# Motherboard.net
KiCad netlist of a schematic drawn in EAGLE
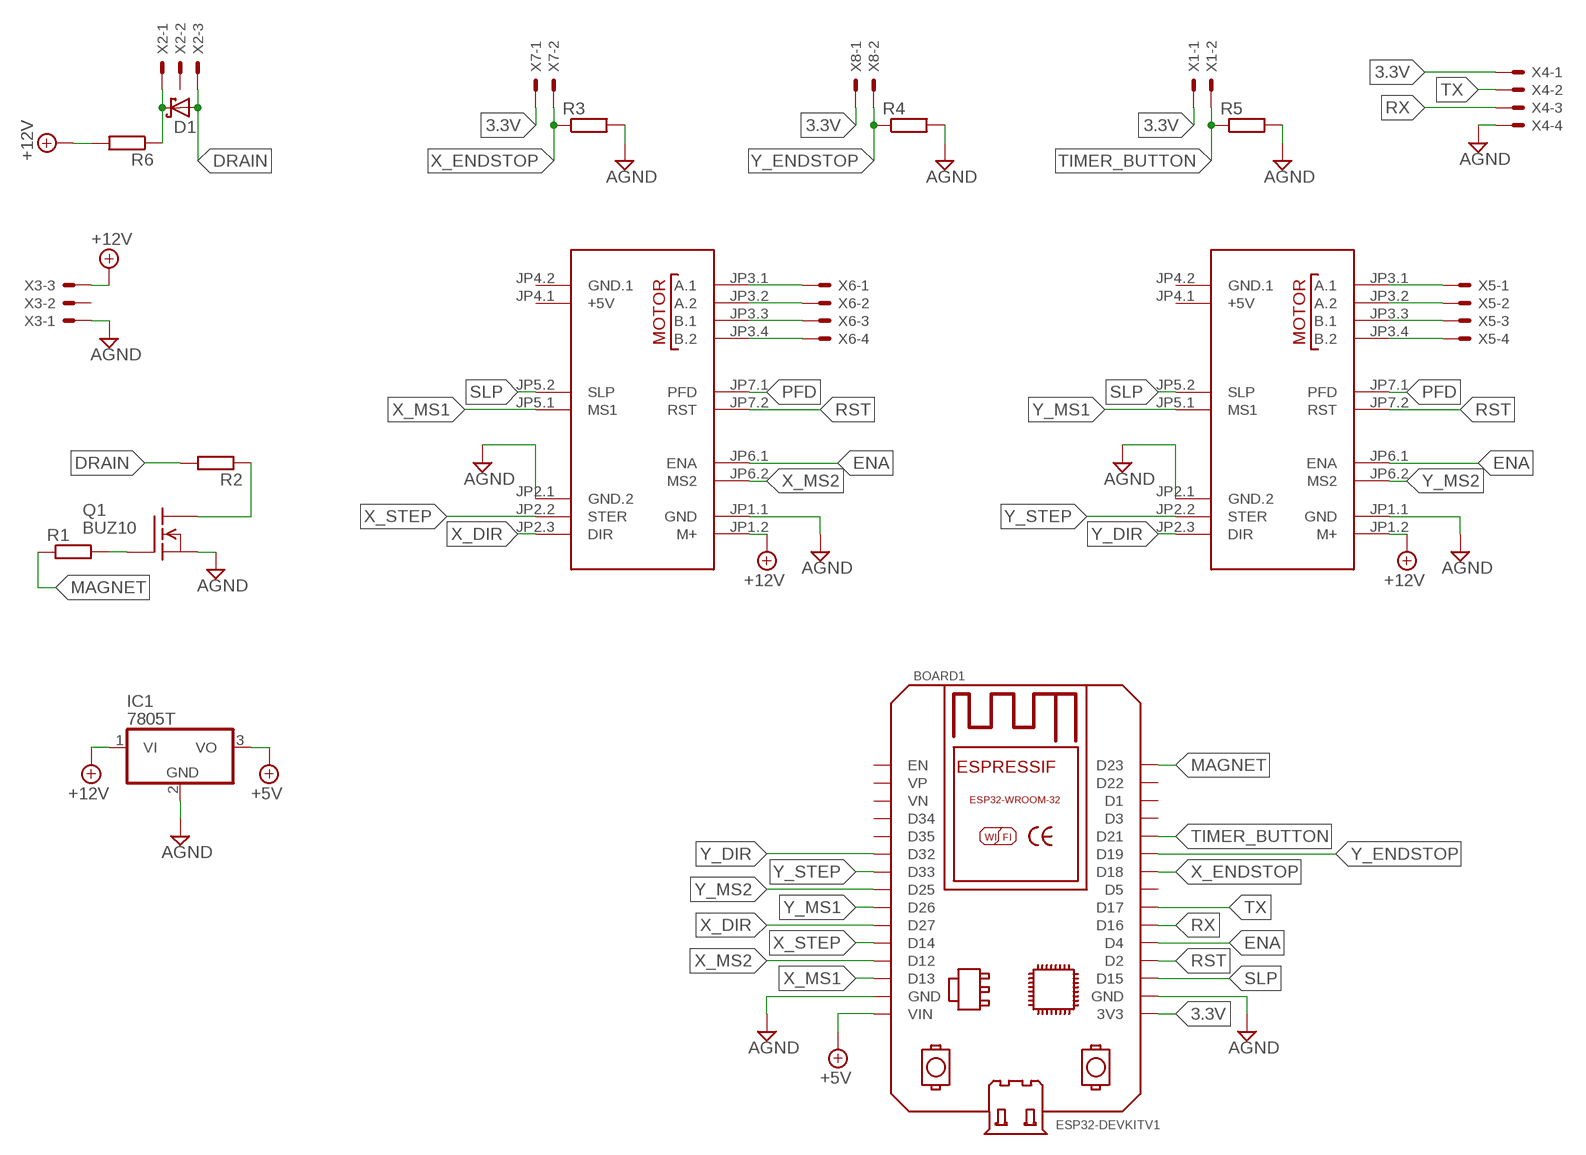
[diagram p0: schematic, sheet 1]

(export (version "E")
  (design (tool "Eeschema 10.0.6"))
  (components
    (comp (ref "BOARD1")
      (value "ESP32DEVKITV1")
      (footprint "eagle-import:ESP32-DEVKITV1")
      (libsource (lib "eagle-import") (part "ESP32DEVKITV1"))
    )
    (comp (ref "D1")
      (value "SCHOTTKY-DIODECB417-15")
      (footprint "eagle-import:CB417-15")
      (libsource (lib "eagle-import") (part "SCHOTTKY-DIODECB417-15"))
    )
    (comp (ref "IC1")
      (value "7805T")
      (footprint "eagle-import:TO220H")
      (libsource (lib "eagle-import") (part "78T05"))
    )
    (comp (ref "Q1")
      (value "BUZ10")
      (footprint "eagle-import:TO220")
      (libsource (lib "eagle-import") (part "BUZ10"))
    )
    (comp (ref "R1")
      (value "R-EU_R0603")
      (footprint "eagle-import:R0603")
      (libsource (lib "eagle-import") (part "R-EU_R0603"))
    )
    (comp (ref "R2")
      (value "R-EU_R0603")
      (footprint "eagle-import:R0603")
      (libsource (lib "eagle-import") (part "R-EU_R0603"))
    )
    (comp (ref "R3")
      (value "R-EU_R0603")
      (footprint "eagle-import:R0603")
      (libsource (lib "eagle-import") (part "R-EU_R0603"))
    )
    (comp (ref "R4")
      (value "R-EU_R0603")
      (footprint "eagle-import:R0603")
      (libsource (lib "eagle-import") (part "R-EU_R0603"))
    )
    (comp (ref "R5")
      (value "R-EU_R0603")
      (footprint "eagle-import:R0603")
      (libsource (lib "eagle-import") (part "R-EU_R0603"))
    )
    (comp (ref "R6")
      (value "R-EU_R0603")
      (footprint "eagle-import:R0603")
      (libsource (lib "eagle-import") (part "R-EU_R0603"))
    )
    (comp (ref "U$1")
      (value "STEPPER-MOTOR-EASY-DRIVER")
      (footprint "eagle-import:STEPPER-MOTOR-EASY-DRIVER")
      (libsource (lib "eagle-import") (part "STEPPER-MOTOR-EASY-DRIVER"))
    )
    (comp (ref "U$2")
      (value "STEPPER-MOTOR-EASY-DRIVER")
      (footprint "eagle-import:STEPPER-MOTOR-EASY-DRIVER")
      (libsource (lib "eagle-import") (part "STEPPER-MOTOR-EASY-DRIVER"))
    )
    (comp (ref "X1")
      (value "22-23-2021")
      (footprint "eagle-import:22-23-2021")
      (fields (field (name "MF") "MOLEX"))
      (libsource (lib "eagle-import") (part "22-23-2021"))
    )
    (comp (ref "X2")
      (value "22-23-2031")
      (footprint "eagle-import:22-23-2031")
      (fields (field (name "MF") "MOLEX"))
      (libsource (lib "eagle-import") (part "22-23-2031"))
    )
    (comp (ref "X3")
      (value "22-23-2031")
      (footprint "eagle-import:22-23-2031")
      (fields (field (name "MF") "MOLEX"))
      (libsource (lib "eagle-import") (part "22-23-2031"))
    )
    (comp (ref "X4")
      (value "22-23-2041")
      (footprint "eagle-import:22-23-2041")
      (fields (field (name "MF") "MOLEX"))
      (libsource (lib "eagle-import") (part "22-23-2041"))
    )
    (comp (ref "X5")
      (value "22-23-2041")
      (footprint "eagle-import:22-23-2041")
      (fields (field (name "MF") "MOLEX"))
      (libsource (lib "eagle-import") (part "22-23-2041"))
    )
    (comp (ref "X6")
      (value "22-23-2041")
      (footprint "eagle-import:22-23-2041")
      (fields (field (name "MF") "MOLEX"))
      (libsource (lib "eagle-import") (part "22-23-2041"))
    )
    (comp (ref "X7")
      (value "22-23-2021")
      (footprint "eagle-import:22-23-2021")
      (fields (field (name "MF") "MOLEX"))
      (libsource (lib "eagle-import") (part "22-23-2021"))
    )
    (comp (ref "X8")
      (value "22-23-2021")
      (footprint "eagle-import:22-23-2021")
      (fields (field (name "MF") "MOLEX"))
      (libsource (lib "eagle-import") (part "22-23-2021"))
    )
  )
  (nets
    (net (code "1") (name "+5V") (class "Default")
      (node (ref "BOARD1") (pin "VIN") (pinfunction "VIN_VIN") (pintype "bidirectional"))
      (node (ref "IC1") (pin "3") (pinfunction "VO_3") (pintype "passive"))
    )
    (net (code "2") (name "+12V") (class "Default")
      (node (ref "IC1") (pin "1") (pinfunction "VI_1") (pintype "input"))
      (node (ref "R6") (pin "2") (pinfunction "2_2") (pintype "passive"))
      (node (ref "U$1") (pin "JP1.2") (pinfunction "M+_JP1.2") (pintype "bidirectional"))
      (node (ref "U$2") (pin "JP1.2") (pinfunction "M+_JP1.2") (pintype "bidirectional"))
      (node (ref "X3") (pin "3") (pinfunction "S_3") (pintype "passive"))
    )
    (net (code "3") (name "3.3V") (class "Default")
      (node (ref "BOARD1") (pin "3V3") (pinfunction "3V3_3V3") (pintype "bidirectional"))
      (node (ref "X1") (pin "1") (pinfunction "S_1") (pintype "passive"))
      (node (ref "X4") (pin "1") (pinfunction "S_1") (pintype "passive"))
      (node (ref "X7") (pin "1") (pinfunction "S_1") (pintype "passive"))
      (node (ref "X8") (pin "1") (pinfunction "S_1") (pintype "passive"))
    )
    (net (code "4") (name "AGND") (class "Default")
      (node (ref "BOARD1") (pin "GND") (pinfunction "GND_GND") (pintype "bidirectional"))
      (node (ref "BOARD1") (pin "GND@1") (pinfunction "GND_GND@1") (pintype "bidirectional"))
      (node (ref "IC1") (pin "2") (pinfunction "GND_2") (pintype "passive"))
      (node (ref "Q1") (pin "3") (pinfunction "S_3") (pintype "passive"))
      (node (ref "R3") (pin "2") (pinfunction "2_2") (pintype "passive"))
      (node (ref "R4") (pin "2") (pinfunction "2_2") (pintype "passive"))
      (node (ref "R5") (pin "2") (pinfunction "2_2") (pintype "passive"))
      (node (ref "U$1") (pin "JP1.1") (pinfunction "GND_JP1.1") (pintype "bidirectional"))
      (node (ref "U$1") (pin "JP2.1") (pinfunction "GND.2_JP2.1") (pintype "bidirectional"))
      (node (ref "U$2") (pin "JP1.1") (pinfunction "GND_JP1.1") (pintype "bidirectional"))
      (node (ref "U$2") (pin "JP2.1") (pinfunction "GND.2_JP2.1") (pintype "bidirectional"))
      (node (ref "X3") (pin "1") (pinfunction "S_1") (pintype "passive"))
      (node (ref "X4") (pin "4") (pinfunction "S_4") (pintype "passive"))
    )
    (net (code "5") (name "DRAIN") (class "Default")
      (node (ref "D1") (pin "A") (pinfunction "A_A") (pintype "passive"))
      (node (ref "R2") (pin "2") (pinfunction "2_2") (pintype "passive"))
      (node (ref "X2") (pin "3") (pinfunction "S_3") (pintype "passive"))
    )
    (net (code "6") (name "ENA") (class "Default")
      (node (ref "BOARD1") (pin "D4") (pinfunction "D4_D4") (pintype "bidirectional"))
      (node (ref "U$1") (pin "JP6.1") (pinfunction "ENA_JP6.1") (pintype "bidirectional"))
      (node (ref "U$2") (pin "JP6.1") (pinfunction "ENA_JP6.1") (pintype "bidirectional"))
    )
    (net (code "7") (name "MAGNET") (class "Default")
      (node (ref "BOARD1") (pin "D23") (pinfunction "D23_D23") (pintype "bidirectional"))
      (node (ref "R1") (pin "1") (pinfunction "1_1") (pintype "passive"))
    )
    (net (code "8") (name "Net-(Q1-D)") (class "Default")
      (node (ref "Q1") (pin "2") (pinfunction "D_2") (pintype "passive"))
      (node (ref "R2") (pin "1") (pinfunction "1_1") (pintype "passive"))
    )
    (net (code "9") (name "Net-(Q1-G)") (class "Default")
      (node (ref "Q1") (pin "1") (pinfunction "G_1") (pintype "passive"))
      (node (ref "R1") (pin "2") (pinfunction "2_2") (pintype "passive"))
    )
    (net (code "10") (name "Net-(U$1-A.1)") (class "Default")
      (node (ref "U$1") (pin "JP3.1") (pinfunction "A.1_JP3.1") (pintype "bidirectional"))
      (node (ref "X6") (pin "1") (pinfunction "S_1") (pintype "passive"))
    )
    (net (code "11") (name "Net-(U$1-A.2)") (class "Default")
      (node (ref "U$1") (pin "JP3.2") (pinfunction "A.2_JP3.2") (pintype "bidirectional"))
      (node (ref "X6") (pin "2") (pinfunction "S_2") (pintype "passive"))
    )
    (net (code "12") (name "Net-(U$1-B.1)") (class "Default")
      (node (ref "U$1") (pin "JP3.3") (pinfunction "B.1_JP3.3") (pintype "bidirectional"))
      (node (ref "X6") (pin "3") (pinfunction "S_3") (pintype "passive"))
    )
    (net (code "13") (name "Net-(U$1-B.2)") (class "Default")
      (node (ref "U$1") (pin "JP3.4") (pinfunction "B.2_JP3.4") (pintype "bidirectional"))
      (node (ref "X6") (pin "4") (pinfunction "S_4") (pintype "passive"))
    )
    (net (code "14") (name "Net-(U$2-A.1)") (class "Default")
      (node (ref "U$2") (pin "JP3.1") (pinfunction "A.1_JP3.1") (pintype "bidirectional"))
      (node (ref "X5") (pin "1") (pinfunction "S_1") (pintype "passive"))
    )
    (net (code "15") (name "Net-(U$2-A.2)") (class "Default")
      (node (ref "U$2") (pin "JP3.2") (pinfunction "A.2_JP3.2") (pintype "bidirectional"))
      (node (ref "X5") (pin "2") (pinfunction "S_2") (pintype "passive"))
    )
    (net (code "16") (name "Net-(U$2-B.1)") (class "Default")
      (node (ref "U$2") (pin "JP3.3") (pinfunction "B.1_JP3.3") (pintype "bidirectional"))
      (node (ref "X5") (pin "3") (pinfunction "S_3") (pintype "passive"))
    )
    (net (code "17") (name "Net-(U$2-B.2)") (class "Default")
      (node (ref "U$2") (pin "JP3.4") (pinfunction "B.2_JP3.4") (pintype "bidirectional"))
      (node (ref "X5") (pin "4") (pinfunction "S_4") (pintype "passive"))
    )
    (net (code "18") (name "Net-(X2A-S)") (class "Default")
      (node (ref "D1") (pin "C") (pinfunction "C_C") (pintype "passive"))
      (node (ref "R6") (pin "1") (pinfunction "1_1") (pintype "passive"))
      (node (ref "X2") (pin "1") (pinfunction "S_1") (pintype "passive"))
    )
    (net (code "19") (name "PFD") (class "Default")
      (node (ref "U$1") (pin "JP7.1") (pinfunction "PFD_JP7.1") (pintype "bidirectional"))
      (node (ref "U$2") (pin "JP7.1") (pinfunction "PFD_JP7.1") (pintype "bidirectional"))
    )
    (net (code "20") (name "RST") (class "Default")
      (node (ref "BOARD1") (pin "D2") (pinfunction "D2_D2") (pintype "bidirectional"))
      (node (ref "U$1") (pin "JP7.2") (pinfunction "RST_JP7.2") (pintype "bidirectional"))
      (node (ref "U$2") (pin "JP7.2") (pinfunction "RST_JP7.2") (pintype "bidirectional"))
    )
    (net (code "21") (name "RX") (class "Default")
      (node (ref "BOARD1") (pin "D16") (pinfunction "D16_D16") (pintype "bidirectional"))
      (node (ref "X4") (pin "3") (pinfunction "S_3") (pintype "passive"))
    )
    (net (code "22") (name "SLP") (class "Default")
      (node (ref "BOARD1") (pin "D15") (pinfunction "D15_D15") (pintype "bidirectional"))
      (node (ref "U$1") (pin "JP5.2") (pinfunction "SLP_JP5.2") (pintype "bidirectional"))
      (node (ref "U$2") (pin "JP5.2") (pinfunction "SLP_JP5.2") (pintype "bidirectional"))
    )
    (net (code "23") (name "TIMER_BUTTON") (class "Default")
      (node (ref "BOARD1") (pin "D21") (pinfunction "D21_D21") (pintype "bidirectional"))
      (node (ref "R5") (pin "1") (pinfunction "1_1") (pintype "passive"))
      (node (ref "X1") (pin "2") (pinfunction "S_2") (pintype "passive"))
    )
    (net (code "24") (name "TX") (class "Default")
      (node (ref "BOARD1") (pin "D17") (pinfunction "D17_D17") (pintype "bidirectional"))
      (node (ref "X4") (pin "2") (pinfunction "S_2") (pintype "passive"))
    )
    (net (code "25") (name "X_DIR") (class "Default")
      (node (ref "BOARD1") (pin "D27") (pinfunction "D27_D27") (pintype "bidirectional"))
      (node (ref "U$1") (pin "JP2.3") (pinfunction "DIR_JP2.3") (pintype "bidirectional"))
    )
    (net (code "26") (name "X_ENDSTOP") (class "Default")
      (node (ref "BOARD1") (pin "D18") (pinfunction "D18_D18") (pintype "bidirectional"))
      (node (ref "R3") (pin "1") (pinfunction "1_1") (pintype "passive"))
      (node (ref "X7") (pin "2") (pinfunction "S_2") (pintype "passive"))
    )
    (net (code "27") (name "X_MS1") (class "Default")
      (node (ref "BOARD1") (pin "D13") (pinfunction "D13_D13") (pintype "bidirectional"))
      (node (ref "U$1") (pin "JP5.1") (pinfunction "MS1_JP5.1") (pintype "bidirectional"))
    )
    (net (code "28") (name "X_MS2") (class "Default")
      (node (ref "BOARD1") (pin "D12") (pinfunction "D12_D12") (pintype "bidirectional"))
      (node (ref "U$1") (pin "JP6.2") (pinfunction "MS2_JP6.2") (pintype "bidirectional"))
    )
    (net (code "29") (name "X_STEP") (class "Default")
      (node (ref "BOARD1") (pin "D14") (pinfunction "D14_D14") (pintype "bidirectional"))
      (node (ref "U$1") (pin "JP2.2") (pinfunction "STER_JP2.2") (pintype "bidirectional"))
    )
    (net (code "30") (name "Y_DIR") (class "Default")
      (node (ref "BOARD1") (pin "D32") (pinfunction "D32_D32") (pintype "bidirectional"))
      (node (ref "U$2") (pin "JP2.3") (pinfunction "DIR_JP2.3") (pintype "bidirectional"))
    )
    (net (code "31") (name "Y_ENDSTOP") (class "Default")
      (node (ref "BOARD1") (pin "D19") (pinfunction "D19_D19") (pintype "bidirectional"))
      (node (ref "R4") (pin "1") (pinfunction "1_1") (pintype "passive"))
      (node (ref "X8") (pin "2") (pinfunction "S_2") (pintype "passive"))
    )
    (net (code "32") (name "Y_MS1") (class "Default")
      (node (ref "BOARD1") (pin "D26") (pinfunction "D26_D26") (pintype "bidirectional"))
      (node (ref "U$2") (pin "JP5.1") (pinfunction "MS1_JP5.1") (pintype "bidirectional"))
    )
    (net (code "33") (name "Y_MS2") (class "Default")
      (node (ref "BOARD1") (pin "D25") (pinfunction "D25_D25") (pintype "bidirectional"))
      (node (ref "U$2") (pin "JP6.2") (pinfunction "MS2_JP6.2") (pintype "bidirectional"))
    )
    (net (code "34") (name "Y_STEP") (class "Default")
      (node (ref "BOARD1") (pin "D33") (pinfunction "D33_D33") (pintype "bidirectional"))
      (node (ref "U$2") (pin "JP2.2") (pinfunction "STER_JP2.2") (pintype "bidirectional"))
    )
    (net (code "35") (name "unconnected-(BOARD1-PadD1)") (class "Default")
      (node (ref "BOARD1") (pin "D1") (pinfunction "D1_D1") (pintype "bidirectional"))
    )
    (net (code "36") (name "unconnected-(BOARD1-PadD3)") (class "Default")
      (node (ref "BOARD1") (pin "D3") (pinfunction "D3_D3") (pintype "bidirectional"))
    )
    (net (code "37") (name "unconnected-(BOARD1-PadD5)") (class "Default")
      (node (ref "BOARD1") (pin "D5") (pinfunction "D5_D5") (pintype "bidirectional"))
    )
    (net (code "38") (name "unconnected-(BOARD1-PadD22)") (class "Default")
      (node (ref "BOARD1") (pin "D22") (pinfunction "D22_D22") (pintype "bidirectional"))
    )
    (net (code "39") (name "unconnected-(BOARD1-PadD34)") (class "Default")
      (node (ref "BOARD1") (pin "D34") (pinfunction "D34_D34") (pintype "bidirectional"))
    )
    (net (code "40") (name "unconnected-(BOARD1-PadD35)") (class "Default")
      (node (ref "BOARD1") (pin "D35") (pinfunction "D35_D35") (pintype "bidirectional"))
    )
    (net (code "41") (name "unconnected-(BOARD1-PadEN)") (class "Default")
      (node (ref "BOARD1") (pin "EN") (pinfunction "EN_EN") (pintype "bidirectional"))
    )
    (net (code "42") (name "unconnected-(BOARD1-PadVN)") (class "Default")
      (node (ref "BOARD1") (pin "VN") (pinfunction "VN_VN") (pintype "bidirectional"))
    )
    (net (code "43") (name "unconnected-(BOARD1-PadVP)") (class "Default")
      (node (ref "BOARD1") (pin "VP") (pinfunction "VP_VP") (pintype "bidirectional"))
    )
    (net (code "44") (name "unconnected-(U$1-+5V-PadJP4.1)") (class "Default")
      (node (ref "U$1") (pin "JP4.1") (pinfunction "+5V_JP4.1") (pintype "bidirectional"))
    )
    (net (code "45") (name "unconnected-(U$1-GND.1-PadJP4.2)") (class "Default")
      (node (ref "U$1") (pin "JP4.2") (pinfunction "GND.1_JP4.2") (pintype "bidirectional"))
    )
    (net (code "46") (name "unconnected-(U$2-+5V-PadJP4.1)") (class "Default")
      (node (ref "U$2") (pin "JP4.1") (pinfunction "+5V_JP4.1") (pintype "bidirectional"))
    )
    (net (code "47") (name "unconnected-(U$2-GND.1-PadJP4.2)") (class "Default")
      (node (ref "U$2") (pin "JP4.2") (pinfunction "GND.1_JP4.2") (pintype "bidirectional"))
    )
    (net (code "48") (name "unconnected-(X2B-S-Pad2)") (class "Default")
      (node (ref "X2") (pin "2") (pinfunction "S_2") (pintype "passive"))
    )
    (net (code "49") (name "unconnected-(X3B-S-Pad2)") (class "Default")
      (node (ref "X3") (pin "2") (pinfunction "S_2") (pintype "passive"))
    )
  )
)
